# HEATER_CTRL.net
KiCad netlist of a schematic drawn in Altium Designer
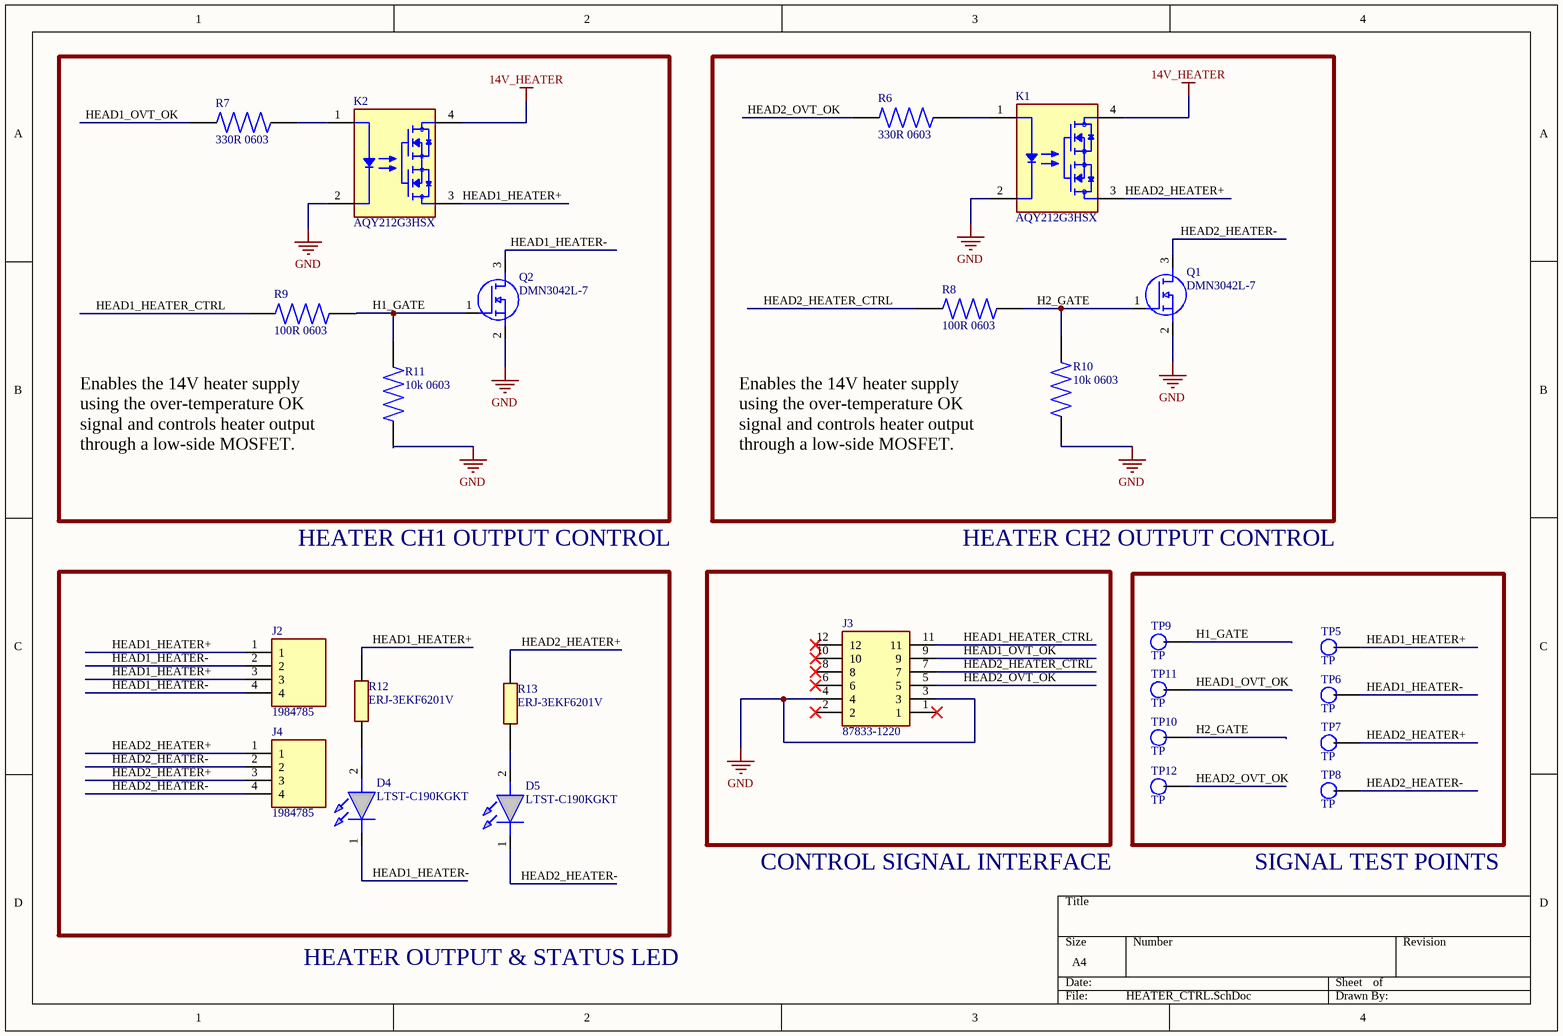
[diagram p0: HEATER_CTRL.SchDoc]

(export (version "E")
  (design (tool "Eeschema 10.0.6"))
  (components
    (comp (ref "D4")
      (value "LTST-C190KGKT")
      (footprint "LEDC1608X80N")
      (description "Lite-On LTST-C190KGKT, 571 nm Green LED, 1608 (0603) SMD package")
      (fields (field (name "MOUSER PART NUMBER") "859-LTST-C190KGKT"))
      (libsource (lib "LTST-C190KGKT") (part "LTST-C190KGKT"))
    )
    (comp (ref "D5")
      (value "LTST-C190KGKT")
      (footprint "LEDC1608X80N")
      (description "Lite-On LTST-C190KGKT, 571 nm Green LED, 1608 (0603) SMD package")
      (fields (field (name "MOUSER PART NUMBER") "859-LTST-C190KGKT"))
      (libsource (lib "LTST-C190KGKT") (part "LTST-C190KGKT"))
    )
    (comp (ref "J2")
      (value "1984785")
      (footprint "1984785")
      (fields (field (name "MOUSER PART NUMBER") "651-1984785"))
      (libsource (lib "1984785") (part "1984785"))
    )
    (comp (ref "J3")
      (value "87833-1220")
      (footprint "SHDRRA12W55P200_2X6_1465X640X630P")
      (description "MOLEX - 87833-1220 - HEADER, MILLI-GRID, 2MM, THD, R/A, 12WAY")
      (fields (field (name "MOUSER PART NUMBER") "538-87833-1220"))
      (libsource (lib "87833-1220") (part "87833-1220"))
    )
    (comp (ref "J4")
      (value "1984785")
      (footprint "1984785")
      (fields (field (name "MOUSER PART NUMBER") "651-1984785"))
      (libsource (lib "1984785") (part "1984785"))
    )
    (comp (ref "K1")
      (value "AQY212G3HSX")
      (footprint "SOIC254P680X230-4N")
      (description "Solid State Photo-Coupled Relay (Photorelay) SPST-NO (1 Form A) 4-SMD, Gull Wing")
      (fields (field (name "MF") "Panasonic"))
      (libsource (lib "AQY212G3HSX") (part "AQY212G3HSX"))
    )
    (comp (ref "K2")
      (value "AQY212G3HSX")
      (footprint "SOIC254P680X230-4N")
      (description "Solid State Photo-Coupled Relay (Photorelay) SPST-NO (1 Form A) 4-SMD, Gull Wing")
      (fields (field (name "MF") "Panasonic"))
      (libsource (lib "AQY212G3HSX") (part "AQY212G3HSX"))
    )
    (comp (ref "Q1")
      (value "DMN3042L-7")
      (footprint "SOT96P240X115-3N")
      (description "MOSFET 30V N-Ch Enh Mode 26.5mOhm 10V 5.8A")
      (fields (field (name "MOUSER PART NUMBER") "621-DMN3042L-7"))
      (libsource (lib "DMN3042L-7") (part "DMN3042L-7"))
    )
    (comp (ref "Q2")
      (value "DMN3042L-7")
      (footprint "SOT96P240X115-3N")
      (description "MOSFET 30V N-Ch Enh Mode 26.5mOhm 10V 5.8A")
      (fields (field (name "MOUSER PART NUMBER") "621-DMN3042L-7"))
      (libsource (lib "DMN3042L-7") (part "DMN3042L-7"))
    )
    (comp (ref "R6")
      (value "330R 0603")
      (footprint "RES_ERJ3EKF3300V")
      (description "Res Thick Film 0603 330 Ohm 1% 0.1W(1/10W) 100ppm/C Molded SMD Punched Carrier T/R")
      (fields (field (name "MF") "Panasonic") (field (name "MP") "ERJ-3EKF3300V"))
      (libsource (lib "ERJ3EKF3300V") (part "ERJ3EKF3300V"))
    )
    (comp (ref "R7")
      (value "330R 0603")
      (footprint "RES_ERJ3EKF3300V")
      (description "Res Thick Film 0603 330 Ohm 1% 0.1W(1/10W) 100ppm/C Molded SMD Punched Carrier T/R")
      (fields (field (name "MF") "Panasonic") (field (name "MP") "ERJ-3EKF3300V"))
      (libsource (lib "ERJ3EKF3300V") (part "ERJ3EKF3300V"))
    )
    (comp (ref "R8")
      (value "100R 0603")
      (footprint "RES_ERJ3EKF1000V")
      (description "100 Ohms 1% 0.1W, 1/10W Chip Resistor 0603 (1608 Metric) Automotive AEC-Q200 Thick Film")
      (fields (field (name "MF") "Panasonic") (field (name "MP") "ERJ-3EKF1000V"))
      (libsource (lib "ERJ3EKF1000V") (part "ERJ3EKF1000V"))
    )
    (comp (ref "R9")
      (value "100R 0603")
      (footprint "RES_ERJ3EKF1000V")
      (description "100 Ohms 1% 0.1W, 1/10W Chip Resistor 0603 (1608 Metric) Automotive AEC-Q200 Thick Film")
      (fields (field (name "MF") "Panasonic") (field (name "MP") "ERJ-3EKF1000V"))
      (libsource (lib "ERJ3EKF1000V") (part "ERJ3EKF1000V"))
    )
    (comp (ref "R10")
      (value "10k 0603")
      (footprint "RES_ERJ3EKF1002V")
      (description "10 kOhms 1% 0.1W, 1/10W Chip Resistor 0603 (1608 Metric) Automotive AEC-Q200 Thick Film")
      (fields (field (name "MF") "Panasonic") (field (name "MP") "ERJ-3EKF1002V"))
      (libsource (lib "ERJ3EKF1002V") (part "ERJ3EKF1002V"))
    )
    (comp (ref "R11")
      (value "10k 0603")
      (footprint "RES_ERJ3EKF1002V")
      (description "10 kOhms 1% 0.1W, 1/10W Chip Resistor 0603 (1608 Metric) Automotive AEC-Q200 Thick Film")
      (fields (field (name "MF") "Panasonic") (field (name "MP") "ERJ-3EKF1002V"))
      (libsource (lib "ERJ3EKF1002V") (part "ERJ3EKF1002V"))
    )
    (comp (ref "R12")
      (value "ERJ-3EKF6201V")
      (footprint "RESC1608X55N")
      (description "Precision Thick Film Chip Resistor, 0603, 0.1W")
      (fields (field (name "MOUSER PART NUMBER") "667-ERJ-3EKF6201V"))
      (libsource (lib "ERJ-3EKF6201V") (part "ERJ-3EKF6201V"))
    )
    (comp (ref "R13")
      (value "ERJ-3EKF6201V")
      (footprint "RESC1608X55N")
      (description "Precision Thick Film Chip Resistor, 0603, 0.1W")
      (fields (field (name "MOUSER PART NUMBER") "667-ERJ-3EKF6201V"))
      (libsource (lib "ERJ-3EKF6201V") (part "ERJ-3EKF6201V"))
    )
    (comp (ref "TP5") (value "TP") (footprint "TESTPOINT") (libsource (lib "TESTPOINT") (part "TP")))
    (comp (ref "TP6") (value "TP") (footprint "TESTPOINT") (libsource (lib "TESTPOINT") (part "TP")))
    (comp (ref "TP7") (value "TP") (footprint "TESTPOINT") (libsource (lib "TESTPOINT") (part "TP")))
    (comp (ref "TP8") (value "TP") (footprint "TESTPOINT") (libsource (lib "TESTPOINT") (part "TP")))
    (comp (ref "TP9") (value "TP") (footprint "TESTPOINT") (libsource (lib "TESTPOINT") (part "TP")))
    (comp (ref "TP10") (value "TP") (footprint "TESTPOINT") (libsource (lib "TESTPOINT") (part "TP")))
    (comp (ref "TP11") (value "TP") (footprint "TESTPOINT") (libsource (lib "TESTPOINT") (part "TP")))
    (comp (ref "TP12") (value "TP") (footprint "TESTPOINT") (libsource (lib "TESTPOINT") (part "TP")))
  )
  (nets
    (net (code "1") (name "/H1_GATE") (class "Default")
      (node (ref "Q2") (pin "1") (pinfunction "G_1") (pintype "passive"))
      (node (ref "R11") (pin "2") (pinfunction "2_2") (pintype "passive"))
      (node (ref "R9") (pin "2") (pinfunction "2_2") (pintype "passive"))
      (node (ref "TP9") (pin "1") (pinfunction "1_1") (pintype "passive"))
    )
    (net (code "2") (name "/H2_GATE") (class "Default")
      (node (ref "Q1") (pin "1") (pinfunction "G_1") (pintype "passive"))
      (node (ref "R10") (pin "2") (pinfunction "2_2") (pintype "passive"))
      (node (ref "R8") (pin "2") (pinfunction "2_2") (pintype "passive"))
      (node (ref "TP10") (pin "1") (pinfunction "1_1") (pintype "passive"))
    )
    (net (code "3") (name "/HEAD1_HEATER+") (class "Default")
      (node (ref "J2") (pin "1") (pinfunction "1_1") (pintype "passive"))
      (node (ref "J2") (pin "3") (pinfunction "3_3") (pintype "passive"))
      (node (ref "K2") (pin "3") (pinfunction "3_3") (pintype "passive"))
      (node (ref "R12") (pin "2") (pinfunction "2_2") (pintype "passive"))
      (node (ref "TP5") (pin "1") (pinfunction "1_1") (pintype "passive"))
    )
    (net (code "4") (name "/HEAD1_HEATER-") (class "Default")
      (node (ref "D4") (pin "1") (pinfunction "K_1") (pintype "passive"))
      (node (ref "J2") (pin "2") (pinfunction "2_2") (pintype "passive"))
      (node (ref "J2") (pin "4") (pinfunction "4_4") (pintype "passive"))
      (node (ref "Q2") (pin "3") (pinfunction "D_3") (pintype "passive"))
      (node (ref "TP6") (pin "1") (pinfunction "1_1") (pintype "passive"))
    )
    (net (code "5") (name "/HEAD1_HEATER_CTRL") (class "Default")
      (node (ref "J3") (pin "11") (pinfunction "11_11") (pintype "passive"))
      (node (ref "R9") (pin "1") (pinfunction "1_1") (pintype "passive"))
    )
    (net (code "6") (name "/HEAD1_OVT_OK") (class "Default")
      (node (ref "J3") (pin "9") (pinfunction "9_9") (pintype "passive"))
      (node (ref "R7") (pin "1") (pinfunction "1_1") (pintype "passive"))
      (node (ref "TP11") (pin "1") (pinfunction "1_1") (pintype "passive"))
    )
    (net (code "7") (name "/HEAD2_HEATER+") (class "Default")
      (node (ref "J4") (pin "1") (pinfunction "1_1") (pintype "passive"))
      (node (ref "J4") (pin "3") (pinfunction "3_3") (pintype "passive"))
      (node (ref "K1") (pin "3") (pinfunction "3_3") (pintype "passive"))
      (node (ref "R13") (pin "2") (pinfunction "2_2") (pintype "passive"))
      (node (ref "TP7") (pin "1") (pinfunction "1_1") (pintype "passive"))
    )
    (net (code "8") (name "/HEAD2_HEATER-") (class "Default")
      (node (ref "D5") (pin "1") (pinfunction "K_1") (pintype "passive"))
      (node (ref "J4") (pin "2") (pinfunction "2_2") (pintype "passive"))
      (node (ref "J4") (pin "4") (pinfunction "4_4") (pintype "passive"))
      (node (ref "Q1") (pin "3") (pinfunction "D_3") (pintype "passive"))
      (node (ref "TP8") (pin "1") (pinfunction "1_1") (pintype "passive"))
    )
    (net (code "9") (name "/HEAD2_HEATER_CTRL") (class "Default")
      (node (ref "J3") (pin "7") (pinfunction "7_7") (pintype "passive"))
      (node (ref "R8") (pin "1") (pinfunction "1_1") (pintype "passive"))
    )
    (net (code "10") (name "/HEAD2_OVT_OK") (class "Default")
      (node (ref "J3") (pin "5") (pinfunction "5_5") (pintype "passive"))
      (node (ref "R6") (pin "1") (pinfunction "1_1") (pintype "passive"))
      (node (ref "TP12") (pin "1") (pinfunction "1_1") (pintype "passive"))
    )
    (net (code "11") (name "14V_HEATER") (class "Default")
      (node (ref "K1") (pin "4") (pinfunction "4_4") (pintype "passive"))
      (node (ref "K2") (pin "4") (pinfunction "4_4") (pintype "passive"))
    )
    (net (code "12") (name "GND") (class "Default")
      (node (ref "J3") (pin "3") (pinfunction "3_3") (pintype "passive"))
      (node (ref "J3") (pin "4") (pinfunction "4_4") (pintype "passive"))
      (node (ref "K1") (pin "2") (pinfunction "2_2") (pintype "passive"))
      (node (ref "K2") (pin "2") (pinfunction "2_2") (pintype "passive"))
      (node (ref "Q1") (pin "2") (pinfunction "S_2") (pintype "passive"))
      (node (ref "Q2") (pin "2") (pinfunction "S_2") (pintype "passive"))
      (node (ref "R10") (pin "1") (pinfunction "1_1") (pintype "passive"))
      (node (ref "R11") (pin "1") (pinfunction "1_1") (pintype "passive"))
    )
    (net (code "13") (name "Net-(D4-A)") (class "Default")
      (node (ref "D4") (pin "2") (pinfunction "A_2") (pintype "passive"))
      (node (ref "R12") (pin "1") (pinfunction "1_1") (pintype "passive"))
    )
    (net (code "14") (name "Net-(D5-A)") (class "Default")
      (node (ref "D5") (pin "2") (pinfunction "A_2") (pintype "passive"))
      (node (ref "R13") (pin "1") (pinfunction "1_1") (pintype "passive"))
    )
    (net (code "15") (name "Net-(K1-Pad1)") (class "Default")
      (node (ref "K1") (pin "1") (pinfunction "1_1") (pintype "passive"))
      (node (ref "R6") (pin "2") (pinfunction "2_2") (pintype "passive"))
    )
    (net (code "16") (name "Net-(K2-Pad1)") (class "Default")
      (node (ref "K2") (pin "1") (pinfunction "1_1") (pintype "passive"))
      (node (ref "R7") (pin "2") (pinfunction "2_2") (pintype "passive"))
    )
    (net (code "17") (name "unconnected-(J3-Pad1)") (class "Default")
      (node (ref "J3") (pin "1") (pinfunction "1_1") (pintype "passive+no_connect"))
    )
    (net (code "18") (name "unconnected-(J3-Pad2)") (class "Default")
      (node (ref "J3") (pin "2") (pinfunction "2_2") (pintype "passive+no_connect"))
    )
    (net (code "19") (name "unconnected-(J3-Pad6)") (class "Default")
      (node (ref "J3") (pin "6") (pinfunction "6_6") (pintype "passive+no_connect"))
    )
    (net (code "20") (name "unconnected-(J3-Pad8)") (class "Default")
      (node (ref "J3") (pin "8") (pinfunction "8_8") (pintype "passive+no_connect"))
    )
    (net (code "21") (name "unconnected-(J3-Pad10)") (class "Default")
      (node (ref "J3") (pin "10") (pinfunction "10_10") (pintype "passive+no_connect"))
    )
    (net (code "22") (name "unconnected-(J3-Pad12)") (class "Default")
      (node (ref "J3") (pin "12") (pinfunction "12_12") (pintype "passive+no_connect"))
    )
  )
)
